# Port.net
KiCad netlist of a schematic drawn in Altium Designer
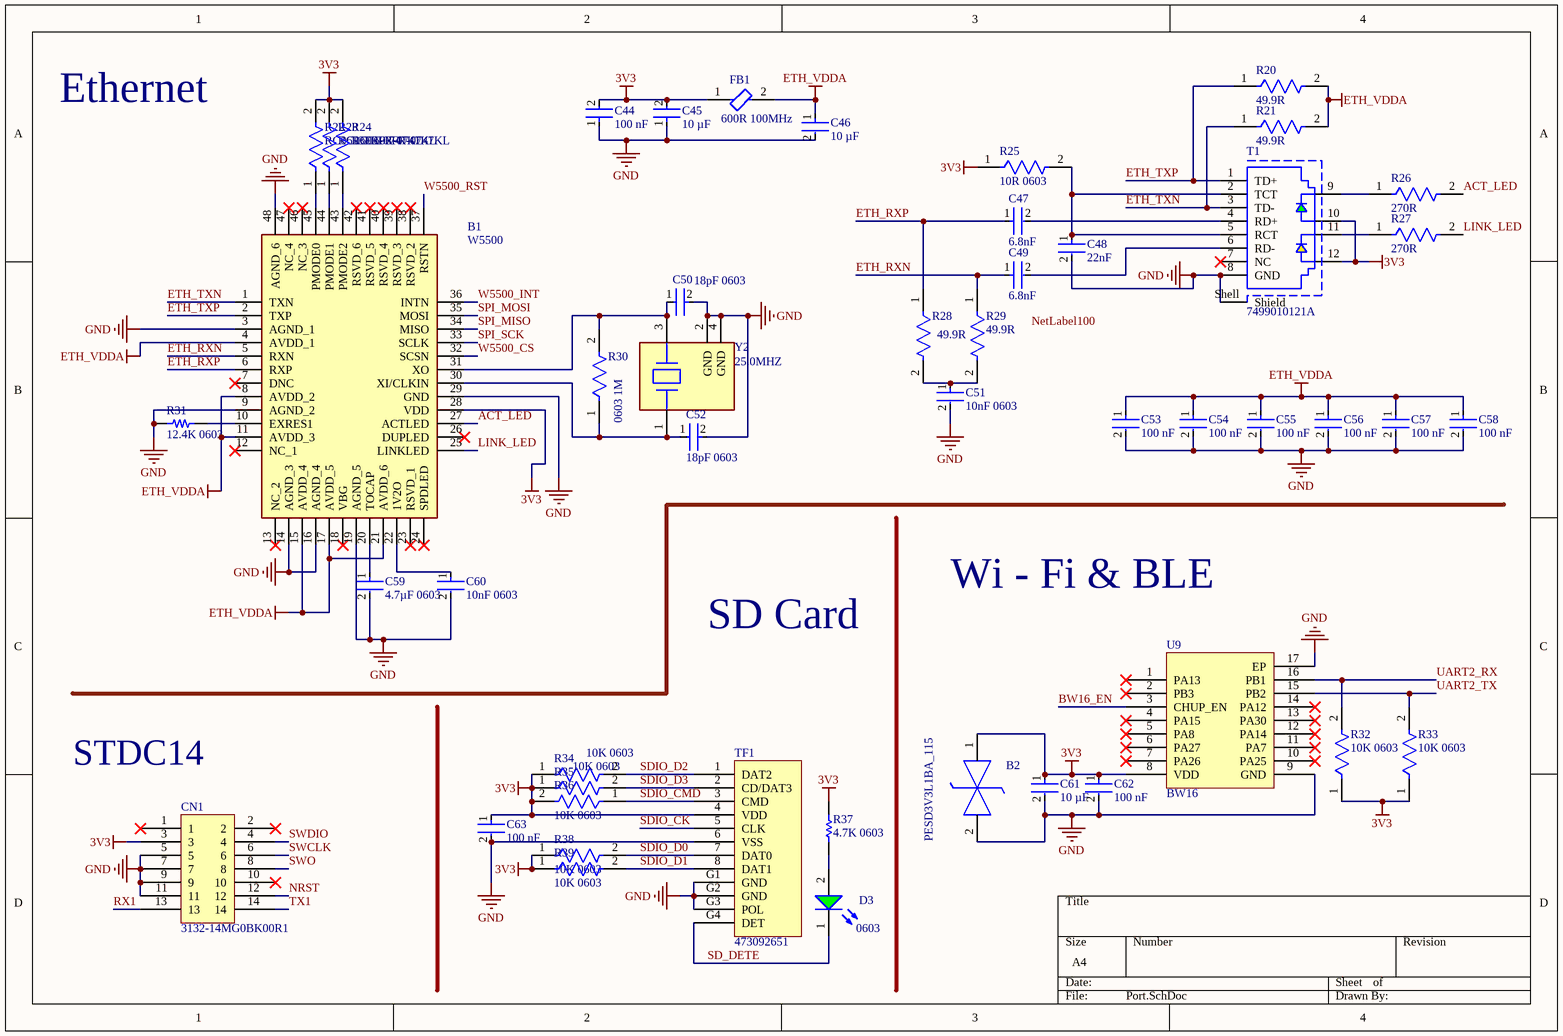
[diagram p0: Port.SchDoc]

(export (version "E")
  (design (tool "Eeschema 10.0.6"))
  (components
    (comp (ref "B1")
      (value "W5500")
      (footprint "W5500")
      (description "Ethernet ICs 3in1 Enet Controller TCP/IP +MAC+PHY")
      (fields (field (name "MOUSER PART NUMBER") "950-W5500"))
      (libsource (lib "Demo") (part "W5500"))
    )
    (comp (ref "B2")
      (value "PESD3V3L1BA_115")
      (footprint "SOD2512X110N")
      (description "PESD3V3L1BA - Low capacitance bidirectional ESD protection diode in SOD323")
      (fields
        (field (name "MANUFACTURER_PART_NUMBER") "PESD3V3L1BA,115")
        (field (name "MOUSER PART NUMBER") "771-PESD3V3L1BA-T/R")
      )
      (libsource (lib "Demo") (part "PESD3V3L1BA_115"))
    )
    (comp (ref "C44")
      (value "100 nF")
      (footprint "FP-CL10-IPC_A")
      (description "Cap Ceramic 100nF 100V X7R ±10% Pad SMD 0603 +125°C T/R")
      (fields (field (name "TOLERANCE") "10%"))
      (libsource (lib "Altium Content Vault") (part "b4654b650e69147ec39a6b967a45e02"))
    )
    (comp (ref "C45")
      (value "10 µF")
      (footprint "FP-CL10-IPC_C")
      (description "Cap Ceramic 10uF 25V X5R ±20% Pad SMD 0603 +85°C T/R")
      (fields (field (name "TOLERANCE") "20%"))
      (libsource (lib "Altium Content Vault") (part "b4654b650e69147ec39a6b967a45e02"))
    )
    (comp (ref "C46")
      (value "10 µF")
      (footprint "FP-CL10-IPC_C")
      (description "Cap Ceramic 10uF 25V X5R ±20% Pad SMD 0603 +85°C T/R")
      (fields (field (name "TOLERANCE") "20%"))
      (libsource (lib "Altium Content Vault") (part "b4654b650e69147ec39a6b967a45e02"))
    )
    (comp (ref "C47")
      (value "6.8nF")
      (footprint "FP-CC0603-DA-MFG")
      (description "CAP CER 6800PF 50V X7R 0603")
      (fields
        (field (name "OCTOPART") "https://octopart.com/cc0603krx7r9bb682-yageo-39467723")
        (field (name "TOLERANCE") "0.1")
      )
      (libsource (lib "Altium Content Vault") (part "11868f565c42a9108669ba33697ecf6"))
    )
    (comp (ref "C48")
      (value "22nF")
      (footprint "FP-CC0603-DA-MFG")
      (description "CAP CER 0.022UF 50V X7R 0603")
      (fields (field (name "TOLERANCE") "10%") (field (name "VOLTAGE") "50V"))
      (libsource (lib "Altium Content Vault") (part "11868f565c42a9108669ba33697ecf6"))
    )
    (comp (ref "C49")
      (value "6.8nF")
      (footprint "FP-CC0603-DA-MFG")
      (description "CAP CER 6800PF 50V X7R 0603")
      (fields
        (field (name "OCTOPART") "https://octopart.com/cc0603krx7r9bb682-yageo-39467723")
        (field (name "TOLERANCE") "0.1")
      )
      (libsource (lib "Altium Content Vault") (part "11868f565c42a9108669ba33697ecf6"))
    )
    (comp (ref "C50")
      (value "18pF 0603")
      (footprint "FP-C1608-080-0_1-IPC_C")
      (description "Multilayer Ceramic Capacitors 18pF ±5% 50V C0G SMD 0603")
      (fields (field (name "VOLTAGE") "50V") (field (name "TOLERANCE") "5%"))
      (libsource (lib "Altium Content Vault") (part "236180d848d6139a670b325ea6854c9"))
    )
    (comp (ref "C51")
      (value "10nF 0603")
      (footprint "FP-CC0603-DA-MFG")
      (description "CAP CER 10000PF 50V X7R 0603")
      (fields (field (name "TOLERANCE") "0.1") (field (name "MANUFACTURER PART NUMBER") "CC0603KRX7R9BB103"))
      (libsource (lib "Altium Content Vault") (part "11868f565c42a9108669ba33697ecf6"))
    )
    (comp (ref "C52")
      (value "18pF 0603")
      (footprint "FP-C1608-080-0_1-IPC_C")
      (description "Multilayer Ceramic Capacitors 18pF ±5% 50V C0G SMD 0603")
      (fields (field (name "VOLTAGE") "50V") (field (name "TOLERANCE") "5%"))
      (libsource (lib "Altium Content Vault") (part "236180d848d6139a670b325ea6854c9"))
    )
    (comp (ref "C53")
      (value "100 nF")
      (footprint "FP-CL10-IPC_A")
      (description "Cap Ceramic 100nF 100V X7R ±10% Pad SMD 0603 +125°C T/R")
      (fields (field (name "TOLERANCE") "10%"))
      (libsource (lib "Altium Content Vault") (part "b4654b650e69147ec39a6b967a45e02"))
    )
    (comp (ref "C54")
      (value "100 nF")
      (footprint "FP-CL10-IPC_A")
      (description "Cap Ceramic 100nF 100V X7R ±10% Pad SMD 0603 +125°C T/R")
      (fields (field (name "TOLERANCE") "10%"))
      (libsource (lib "Altium Content Vault") (part "b4654b650e69147ec39a6b967a45e02"))
    )
    (comp (ref "C55")
      (value "100 nF")
      (footprint "FP-CL10-IPC_A")
      (description "Cap Ceramic 100nF 100V X7R ±10% Pad SMD 0603 +125°C T/R")
      (fields (field (name "TOLERANCE") "10%"))
      (libsource (lib "Altium Content Vault") (part "b4654b650e69147ec39a6b967a45e02"))
    )
    (comp (ref "C56")
      (value "100 nF")
      (footprint "FP-CL10-IPC_A")
      (description "Cap Ceramic 100nF 100V X7R ±10% Pad SMD 0603 +125°C T/R")
      (fields (field (name "TOLERANCE") "10%"))
      (libsource (lib "Altium Content Vault") (part "b4654b650e69147ec39a6b967a45e02"))
    )
    (comp (ref "C57")
      (value "100 nF")
      (footprint "FP-CL10-IPC_A")
      (description "Cap Ceramic 100nF 100V X7R ±10% Pad SMD 0603 +125°C T/R")
      (fields (field (name "TOLERANCE") "10%"))
      (libsource (lib "Altium Content Vault") (part "b4654b650e69147ec39a6b967a45e02"))
    )
    (comp (ref "C58")
      (value "100 nF")
      (footprint "FP-CL10-IPC_A")
      (description "Cap Ceramic 100nF 100V X7R ±10% Pad SMD 0603 +125°C T/R")
      (fields (field (name "TOLERANCE") "10%"))
      (libsource (lib "Altium Content Vault") (part "b4654b650e69147ec39a6b967a45e02"))
    )
    (comp (ref "C59")
      (value "4.7µF 0603")
      (footprint "FP-C0603-CG-MFG")
      (description "CAP CER 4.7UF 6.3V X5R 0603")
      (fields (field (name "TOLERANCE") "10%") (field (name "MANUFACTURER") "Kemet"))
      (libsource (lib "Altium Content Vault") (part "11868f565c42a9108669ba33697ecf6"))
    )
    (comp (ref "C60")
      (value "10nF 0603")
      (footprint "FP-CC0603-DA-MFG")
      (description "CAP CER 10000PF 50V X7R 0603")
      (fields (field (name "TOLERANCE") "0.1") (field (name "MANUFACTURER PART NUMBER") "CC0603KRX7R9BB103"))
      (libsource (lib "Altium Content Vault") (part "11868f565c42a9108669ba33697ecf6"))
    )
    (comp (ref "C61")
      (value "10 µF")
      (footprint "FP-CL10-IPC_C")
      (description "Cap Ceramic 10uF 25V X5R ±20% Pad SMD 0603 +85°C T/R")
      (fields (field (name "TOLERANCE") "20%"))
      (libsource (lib "Altium Content Vault") (part "b4654b650e69147ec39a6b967a45e02"))
    )
    (comp (ref "C62")
      (value "100 nF")
      (footprint "FP-CL10-IPC_A")
      (description "Cap Ceramic 100nF 100V X7R ±10% Pad SMD 0603 +125°C T/R")
      (fields (field (name "TOLERANCE") "10%"))
      (libsource (lib "Altium Content Vault") (part "b4654b650e69147ec39a6b967a45e02"))
    )
    (comp (ref "C63")
      (value "100 nF")
      (footprint "FP-CL10-IPC_A")
      (description "Cap Ceramic 100nF 100V X7R ±10% Pad SMD 0603 +125°C T/R")
      (fields (field (name "TOLERANCE") "10%"))
      (libsource (lib "Altium Content Vault") (part "b4654b650e69147ec39a6b967a45e02"))
    )
    (comp (ref "CN1")
      (value "3132-14MG0BK00R1")
      (footprint "STDC14 Header")
      (libsource (lib "Demo") (part "STDC-14"))
    )
    (comp (ref "D3")
      (value "0603")
      (footprint "WL-SMCW_0603_150060xx75000")
      (libsource (lib "Altium Content Vault") (part "LED_Green_2A-1K"))
    )
    (comp (ref "FB1")
      (value "600R 100MHz")
      (footprint "FP-BLM18-0_15-t0_8-MFG")
      (description "Chip Ferrite Bead, 0603, 600Ω @ 100MHz, 0.38Ω, 25%, 500mA")
      (fields (field (name "TOLERANCE") "25%"))
      (libsource (lib "Altium Content Vault") (part "5f30dd21d616792df468990f7003faa"))
    )
    (comp (ref "R20")
      (value "49.9R")
      (footprint "FP-RT0603-MFG")
      (description "RES SMD 49.9OHM 0.05% 1/10W 0603")
      (fields (field (name "MANUFACTURER") "Yageo") (field (name "TOLERANCE") "0.0005"))
      (libsource (lib "Altium Content Vault") (part "1029c3af85768c4190bb7ad29bc67b5"))
    )
    (comp (ref "R21")
      (value "49.9R")
      (footprint "FP-RT0603-MFG")
      (description "RES SMD 49.9OHM 0.05% 1/10W 0603")
      (fields (field (name "MANUFACTURER") "Yageo") (field (name "TOLERANCE") "0.0005"))
      (libsource (lib "Altium Content Vault") (part "1029c3af85768c4190bb7ad29bc67b5"))
    )
    (comp (ref "R22")
      (value "RC0603FR-0747KL")
      (footprint "FP-RC0603FR-0747KL-MFG")
      (description "RES SMD 47K OHM 1% 1/10W 0603")
      (fields (field (name "TOLERANCE") "1%"))
      (libsource (lib "Altium Content Vault") (part "1029c3af85768c4190bb7ad29bc67b5"))
    )
    (comp (ref "R23")
      (value "RC0603FR-0747KL")
      (footprint "FP-RC0603FR-0747KL-MFG")
      (description "RES SMD 47K OHM 1% 1/10W 0603")
      (fields (field (name "TOLERANCE") "1%"))
      (libsource (lib "Altium Content Vault") (part "1029c3af85768c4190bb7ad29bc67b5"))
    )
    (comp (ref "R24")
      (value "RC0603FR-0747KL")
      (footprint "FP-RC0603FR-0747KL-MFG")
      (description "RES SMD 47K OHM 1% 1/10W 0603")
      (fields (field (name "TOLERANCE") "1%"))
      (libsource (lib "Altium Content Vault") (part "1029c3af85768c4190bb7ad29bc67b5"))
    )
    (comp (ref "R25")
      (value "10R 0603")
      (footprint "FP-RT0603-MFG")
      (description "RES SMD 10 OHM 0.5% 1/10W 0603")
      (fields (field (name "TOLERANCE") "0.005") (field (name "MANUFACTURER") "Yageo"))
      (libsource (lib "Altium Content Vault") (part "1029c3af85768c4190bb7ad29bc67b5"))
    )
    (comp (ref "R26")
      (value "270R")
      (footprint "FP-RT0603-MFG")
      (description "RES SMD 270 OHM 1% 1/10W 0603")
      (fields
        (field (name "OCTOPART") "https://octopart.com/rt0603fre07270rl-yageo-40014674")
        (field (name "TOLERANCE") "0.01")
      )
      (libsource (lib "Altium Content Vault") (part "1029c3af85768c4190bb7ad29bc67b5"))
    )
    (comp (ref "R27")
      (value "270R")
      (footprint "FP-RT0603-MFG")
      (description "RES SMD 270 OHM 1% 1/10W 0603")
      (fields
        (field (name "OCTOPART") "https://octopart.com/rt0603fre07270rl-yageo-40014674")
        (field (name "TOLERANCE") "0.01")
      )
      (libsource (lib "Altium Content Vault") (part "1029c3af85768c4190bb7ad29bc67b5"))
    )
    (comp (ref "R28")
      (value "49.9R")
      (footprint "FP-RT0603-MFG")
      (description "RES SMD 49.9OHM 0.05% 1/10W 0603")
      (fields (field (name "MANUFACTURER") "Yageo") (field (name "TOLERANCE") "0.0005"))
      (libsource (lib "Altium Content Vault") (part "1029c3af85768c4190bb7ad29bc67b5"))
    )
    (comp (ref "R29")
      (value "49.9R")
      (footprint "FP-RT0603-MFG")
      (description "RES SMD 49.9OHM 0.05% 1/10W 0603")
      (fields (field (name "MANUFACTURER") "Yageo") (field (name "TOLERANCE") "0.0005"))
      (libsource (lib "Altium Content Vault") (part "1029c3af85768c4190bb7ad29bc67b5"))
    )
    (comp (ref "R30")
      (value "0603 1M")
      (footprint "FP-RC0603-0_55-IPC_C")
      (description "RES SMD 1M OHM 5% 1/10W 0603")
      (fields (field (name "TOLERANCE") "5%"))
      (libsource (lib "Altium Content Vault") (part "1029c3af85768c4190bb7ad29bc67b5"))
    )
    (comp (ref "R31")
      (value "12.4K 0603")
      (footprint "4.7R")
      (description "SMT Resistor")
      (libsource (lib "Demo") (part "4.7R 0603"))
    )
    (comp (ref "R32")
      (value "10K 0603")
      (footprint "FP-RC0603-0_55-IPC_C")
      (description "RES 10K OHM 1% 1/10W 0603")
      (fields (field (name "TOLERANCE") "1%"))
      (libsource (lib "Altium Content Vault") (part "1029c3af85768c4190bb7ad29bc67b5"))
    )
    (comp (ref "R33")
      (value "10K 0603")
      (footprint "FP-RC0603-0_55-IPC_C")
      (description "RES 10K OHM 1% 1/10W 0603")
      (fields (field (name "TOLERANCE") "1%"))
      (libsource (lib "Altium Content Vault") (part "1029c3af85768c4190bb7ad29bc67b5"))
    )
    (comp (ref "R34")
      (value "10K 0603")
      (footprint "FP-RC0603-0_55-IPC_C")
      (description "RES 10K OHM 1% 1/10W 0603")
      (fields (field (name "TOLERANCE") "1%"))
      (libsource (lib "Altium Content Vault") (part "1029c3af85768c4190bb7ad29bc67b5"))
    )
    (comp (ref "R35")
      (value "10K 0603")
      (footprint "FP-RC0603-0_55-IPC_C")
      (description "RES 10K OHM 1% 1/10W 0603")
      (fields (field (name "TOLERANCE") "1%"))
      (libsource (lib "Altium Content Vault") (part "1029c3af85768c4190bb7ad29bc67b5"))
    )
    (comp (ref "R36")
      (value "10K 0603")
      (footprint "FP-RC0603-0_55-IPC_C")
      (description "RES 10K OHM 1% 1/10W 0603")
      (fields (field (name "TOLERANCE") "1%"))
      (libsource (lib "Altium Content Vault") (part "1029c3af85768c4190bb7ad29bc67b5"))
    )
    (comp (ref "R37")
      (value "4.7K 0603")
      (footprint "RESC1608X55X25LL10T15")
      (description "Chip Resistor, 4.7 KOhm, +/- 1%, 0.1 W, -55 to 155 degC, 0603 (1608 Metric), RoHS, Tape and Reel")
      (fields (field (name "MANUFACTURER") "Yageo") (field (name "TOLERANCE") "1%"))
      (libsource (lib "Altium Content Vault") (part "RES-2"))
    )
    (comp (ref "R38")
      (value "10K 0603")
      (footprint "FP-RC0603-0_55-IPC_C")
      (description "RES 10K OHM 1% 1/10W 0603")
      (fields (field (name "TOLERANCE") "1%"))
      (libsource (lib "Altium Content Vault") (part "1029c3af85768c4190bb7ad29bc67b5"))
    )
    (comp (ref "R39")
      (value "10K 0603")
      (footprint "FP-RC0603-0_55-IPC_C")
      (description "RES 10K OHM 1% 1/10W 0603")
      (fields (field (name "TOLERANCE") "1%"))
      (libsource (lib "Altium Content Vault") (part "1029c3af85768c4190bb7ad29bc67b5"))
    )
    (comp (ref "T1")
      (value "7499010121A")
      (footprint "7499010121A")
      (description "7499010121A Telecom and Datacom Connector, 8 Contact(s), Right Angle, Solder Terminal")
      (libsource (lib "Altium Content Vault") (part "7499010121A"))
    )
    (comp (ref "TF1")
      (value "473092651")
      (footprint "TF-SMD_47309-2285")
      (libsource (lib "Demo") (part "TF-SMD"))
    )
    (comp (ref "U9") (value "BW16") (footprint "BW16") (libsource (lib "Demo") (part "BW16")))
    (comp (ref "Y2")
      (value "25.0MHZ")
      (footprint "FP-ABM8G-MFG")
      (description "Crystal 25MHz ±20ppm (Tol) ±30ppm (Stability) 18pF FUND 60Ω 4-Pin SMD T/R")
      (fields (field (name "TOLERANCE") "20ppm"))
      (libsource (lib "Altium Content Vault") (part "48e526d86b7f2615d98721063c72f49"))
    )
  )
  (nets
    (net (code "1") (name "/ACT_LED") (class "Default")
      (node (ref "B1") (pin "27") (pinfunction "ACTLED_27") (pintype "passive"))
      (node (ref "R26") (pin "2") (pinfunction "2_2") (pintype "passive"))
    )
    (net (code "2") (name "/BW16_EN") (class "Default")
      (node (ref "U9") (pin "3") (pinfunction "CHUP_EN_3") (pintype "passive"))
    )
    (net (code "3") (name "/ETH_RXN") (class "Default")
      (node (ref "B1") (pin "5") (pinfunction "RXN_5") (pintype "passive"))
      (node (ref "C49") (pin "1") (pinfunction "1_1") (pintype "passive"))
      (node (ref "R29") (pin "1") (pinfunction "1_1") (pintype "passive"))
    )
    (net (code "4") (name "/ETH_RXP") (class "Default")
      (node (ref "B1") (pin "6") (pinfunction "RXP_6") (pintype "passive"))
      (node (ref "C47") (pin "1") (pinfunction "1_1") (pintype "passive"))
      (node (ref "R28") (pin "1") (pinfunction "1_1") (pintype "passive"))
    )
    (net (code "5") (name "/ETH_TXN") (class "Default")
      (node (ref "B1") (pin "1") (pinfunction "TXN_1") (pintype "passive"))
      (node (ref "R21") (pin "1") (pinfunction "1_1") (pintype "passive"))
      (node (ref "T1") (pin "3") (pinfunction "TD-_3") (pintype "passive"))
    )
    (net (code "6") (name "/ETH_TXP") (class "Default")
      (node (ref "B1") (pin "2") (pinfunction "TXP_2") (pintype "passive"))
      (node (ref "R20") (pin "1") (pinfunction "1_1") (pintype "passive"))
      (node (ref "T1") (pin "1") (pinfunction "TD+_1") (pintype "passive"))
    )
    (net (code "7") (name "/LINK_LED") (class "Default")
      (node (ref "B1") (pin "25") (pinfunction "LINKLED_25") (pintype "passive"))
      (node (ref "R27") (pin "2") (pinfunction "2_2") (pintype "passive"))
    )
    (net (code "8") (name "/NRST") (class "Default")
      (node (ref "CN1") (pin "12") (pinfunction "12_12") (pintype "passive"))
    )
    (net (code "10") (name "/RX1") (class "Default")
      (node (ref "CN1") (pin "13") (pinfunction "13_13") (pintype "passive"))
    )
    (net (code "11") (name "/SDIO_CK") (class "Default")
      (node (ref "TF1") (pin "5") (pinfunction "CLK_5") (pintype "passive"))
    )
    (net (code "12") (name "/SDIO_CMD") (class "Default")
      (node (ref "R36") (pin "1") (pinfunction "1_1") (pintype "passive"))
      (node (ref "TF1") (pin "3") (pinfunction "CMD_3") (pintype "passive"))
    )
    (net (code "13") (name "/SDIO_D0") (class "Default")
      (node (ref "R38") (pin "2") (pinfunction "2_2") (pintype "passive"))
      (node (ref "TF1") (pin "7") (pinfunction "DAT0_7") (pintype "passive"))
    )
    (net (code "14") (name "/SDIO_D1") (class "Default")
      (node (ref "R39") (pin "2") (pinfunction "2_2") (pintype "passive"))
      (node (ref "TF1") (pin "8") (pinfunction "DAT1_8") (pintype "passive"))
    )
    (net (code "15") (name "/SDIO_D2") (class "Default")
      (node (ref "R34") (pin "2") (pinfunction "2_2") (pintype "passive"))
      (node (ref "TF1") (pin "1") (pinfunction "DAT2_1") (pintype "passive"))
    )
    (net (code "16") (name "/SDIO_D3") (class "Default")
      (node (ref "R35") (pin "2") (pinfunction "2_2") (pintype "passive"))
      (node (ref "TF1") (pin "2") (pinfunction "CD/DAT3_2") (pintype "passive"))
    )
    (net (code "17") (name "/SD_DETE") (class "Default")
      (node (ref "D3") (pin "1") (pinfunction "K_1") (pintype "passive"))
      (node (ref "TF1") (pin "G4") (pinfunction "DET_G4") (pintype "passive"))
    )
    (net (code "18") (name "/SPI_MISO") (class "Default")
      (node (ref "B1") (pin "34") (pinfunction "MISO_34") (pintype "passive"))
    )
    (net (code "19") (name "/SPI_MOSI") (class "Default")
      (node (ref "B1") (pin "35") (pinfunction "MOSI_35") (pintype "passive"))
    )
    (net (code "20") (name "/SPI_SCK") (class "Default")
      (node (ref "B1") (pin "33") (pinfunction "SCLK_33") (pintype "passive"))
    )
    (net (code "21") (name "/SWCLK") (class "Default")
      (node (ref "CN1") (pin "6") (pinfunction "6_6") (pintype "passive"))
    )
    (net (code "22") (name "/SWDIO") (class "Default")
      (node (ref "CN1") (pin "4") (pinfunction "4_4") (pintype "passive"))
    )
    (net (code "23") (name "/SWO") (class "Default")
      (node (ref "CN1") (pin "8") (pinfunction "8_8") (pintype "passive"))
    )
    (net (code "24") (name "/TX1") (class "Default")
      (node (ref "CN1") (pin "14") (pinfunction "14_14") (pintype "passive"))
    )
    (net (code "25") (name "/UART2_RX") (class "Default")
      (node (ref "R32") (pin "2") (pinfunction "2_2") (pintype "passive"))
      (node (ref "U9") (pin "16") (pinfunction "PB1_16") (pintype "passive"))
    )
    (net (code "26") (name "/UART2_TX") (class "Default")
      (node (ref "R33") (pin "2") (pinfunction "2_2") (pintype "passive"))
      (node (ref "U9") (pin "15") (pinfunction "PB2_15") (pintype "passive"))
    )
    (net (code "27") (name "/W5500_CS") (class "Default")
      (node (ref "B1") (pin "32") (pinfunction "SCSN_32") (pintype "passive"))
    )
    (net (code "28") (name "/W5500_INT") (class "Default")
      (node (ref "B1") (pin "36") (pinfunction "INTN_36") (pintype "passive"))
    )
    (net (code "29") (name "/W5500_RST") (class "Default")
      (node (ref "B1") (pin "37") (pinfunction "RSTN_37") (pintype "passive"))
    )
    (net (code "30") (name "3V3") (class "Default")
      (node (ref "B1") (pin "28") (pinfunction "VDD_28") (pintype "passive"))
      (node (ref "B2") (pin "1") (pinfunction "K1_1") (pintype "passive"))
      (node (ref "C44") (pin "2") (pinfunction "2_2") (pintype "passive"))
      (node (ref "C45") (pin "2") (pinfunction "2_2") (pintype "passive"))
      (node (ref "C61") (pin "1") (pinfunction "1_1") (pintype "passive"))
      (node (ref "C62") (pin "1") (pinfunction "1_1") (pintype "passive"))
      (node (ref "C63") (pin "1") (pinfunction "1_1") (pintype "passive"))
      (node (ref "CN1") (pin "3") (pinfunction "3_3") (pintype "passive"))
      (node (ref "FB1") (pin "1") (pinfunction "1_1") (pintype "passive"))
      (node (ref "R22") (pin "2") (pinfunction "2_2") (pintype "passive"))
      (node (ref "R23") (pin "2") (pinfunction "2_2") (pintype "passive"))
      (node (ref "R24") (pin "2") (pinfunction "2_2") (pintype "passive"))
      (node (ref "R25") (pin "1") (pinfunction "1_1") (pintype "passive"))
      (node (ref "R32") (pin "1") (pinfunction "1_1") (pintype "passive"))
      (node (ref "R33") (pin "1") (pinfunction "1_1") (pintype "passive"))
      (node (ref "R34") (pin "1") (pinfunction "1_1") (pintype "passive"))
      (node (ref "R35") (pin "1") (pinfunction "1_1") (pintype "passive"))
      (node (ref "R36") (pin "2") (pinfunction "2_2") (pintype "passive"))
      (node (ref "R37") (pin "1") (pinfunction "1_1") (pintype "passive"))
      (node (ref "R38") (pin "1") (pinfunction "1_1") (pintype "passive"))
      (node (ref "R39") (pin "1") (pinfunction "1_1") (pintype "passive"))
      (node (ref "T1") (pin "10") (pinfunction "10_10") (pintype "passive"))
      (node (ref "T1") (pin "12") (pinfunction "12_12") (pintype "passive"))
      (node (ref "TF1") (pin "4") (pinfunction "VDD_4") (pintype "passive"))
      (node (ref "U9") (pin "8") (pinfunction "VDD_8") (pintype "passive"))
    )
    (net (code "31") (name "ETH_VDDA") (class "Default")
      (node (ref "B1") (pin "11") (pinfunction "AVDD_3_11") (pintype "passive"))
      (node (ref "B1") (pin "15") (pinfunction "AVDD_4_15") (pintype "passive"))
      (node (ref "B1") (pin "17") (pinfunction "AVDD_5_17") (pintype "passive"))
      (node (ref "B1") (pin "21") (pinfunction "AVDD_6_21") (pintype "passive"))
      (node (ref "B1") (pin "4") (pinfunction "AVDD_1_4") (pintype "passive"))
      (node (ref "B1") (pin "8") (pinfunction "AVDD_2_8") (pintype "passive"))
      (node (ref "C46") (pin "1") (pinfunction "1_1") (pintype "passive"))
      (node (ref "C53") (pin "1") (pinfunction "1_1") (pintype "passive"))
      (node (ref "C54") (pin "1") (pinfunction "1_1") (pintype "passive"))
      (node (ref "C55") (pin "1") (pinfunction "1_1") (pintype "passive"))
      (node (ref "C56") (pin "1") (pinfunction "1_1") (pintype "passive"))
      (node (ref "C57") (pin "1") (pinfunction "1_1") (pintype "passive"))
      (node (ref "C58") (pin "1") (pinfunction "1_1") (pintype "passive"))
      (node (ref "FB1") (pin "2") (pinfunction "2_2") (pintype "passive"))
      (node (ref "R20") (pin "2") (pinfunction "2_2") (pintype "passive"))
      (node (ref "R21") (pin "2") (pinfunction "2_2") (pintype "passive"))
    )
    (net (code "32") (name "GND") (class "Default")
      (node (ref "B1") (pin "14") (pinfunction "AGND_3_14") (pintype "passive"))
      (node (ref "B1") (pin "16") (pinfunction "AGND_4_16") (pintype "passive"))
      (node (ref "B1") (pin "19") (pinfunction "AGND_5_19") (pintype "passive"))
      (node (ref "B1") (pin "29") (pinfunction "GND_29") (pintype "passive"))
      (node (ref "B1") (pin "3") (pinfunction "AGND_1_3") (pintype "passive"))
      (node (ref "B1") (pin "48") (pinfunction "AGND_6_48") (pintype "passive"))
      (node (ref "B1") (pin "9") (pinfunction "AGND_2_9") (pintype "passive"))
      (node (ref "B2") (pin "2") (pinfunction "K2_2") (pintype "passive"))
      (node (ref "C44") (pin "1") (pinfunction "1_1") (pintype "passive"))
      (node (ref "C45") (pin "1") (pinfunction "1_1") (pintype "passive"))
      (node (ref "C46") (pin "2") (pinfunction "2_2") (pintype "passive"))
      (node (ref "C48") (pin "2") (pinfunction "2_2") (pintype "passive"))
      (node (ref "C50") (pin "2") (pinfunction "2_2") (pintype "passive"))
      (node (ref "C51") (pin "2") (pinfunction "2_2") (pintype "passive"))
      (node (ref "C52") (pin "2") (pinfunction "2_2") (pintype "passive"))
      (node (ref "C53") (pin "2") (pinfunction "2_2") (pintype "passive"))
      (node (ref "C54") (pin "2") (pinfunction "2_2") (pintype "passive"))
      (node (ref "C55") (pin "2") (pinfunction "2_2") (pintype "passive"))
      (node (ref "C56") (pin "2") (pinfunction "2_2") (pintype "passive"))
      (node (ref "C57") (pin "2") (pinfunction "2_2") (pintype "passive"))
      (node (ref "C58") (pin "2") (pinfunction "2_2") (pintype "passive"))
      (node (ref "C59") (pin "2") (pinfunction "2_2") (pintype "passive"))
      (node (ref "C60") (pin "2") (pinfunction "2_2") (pintype "passive"))
      (node (ref "C61") (pin "2") (pinfunction "2_2") (pintype "passive"))
      (node (ref "C62") (pin "2") (pinfunction "2_2") (pintype "passive"))
      (node (ref "C63") (pin "2") (pinfunction "2_2") (pintype "passive"))
      (node (ref "CN1") (pin "11") (pinfunction "11_11") (pintype "passive"))
      (node (ref "CN1") (pin "5") (pinfunction "5_5") (pintype "passive"))
      (node (ref "CN1") (pin "7") (pinfunction "7_7") (pintype "passive"))
      (node (ref "CN1") (pin "9") (pinfunction "9_9") (pintype "passive"))
      (node (ref "R31") (pin "2") (pinfunction "2_2") (pintype "passive"))
      (node (ref "T1") (pin "8") (pinfunction "GND_8") (pintype "passive"))
      (node (ref "T1") (pin "Shell") (pinfunction "Shield_Shell") (pintype "passive"))
      (node (ref "TF1") (pin "6") (pinfunction "VSS_6") (pintype "passive"))
      (node (ref "TF1") (pin "G1") (pinfunction "GND_G1") (pintype "passive"))
      (node (ref "TF1") (pin "G2") (pinfunction "GND_G2") (pintype "passive"))
      (node (ref "TF1") (pin "G3") (pinfunction "POL_G3") (pintype "passive"))
      (node (ref "U9") (pin "17") (pinfunction "EP_17") (pintype "passive"))
      (node (ref "U9") (pin "9") (pinfunction "GND_9") (pintype "passive"))
      (node (ref "Y2") (pin "2") (pinfunction "GND_2") (pintype "power_in"))
      (node (ref "Y2") (pin "4") (pinfunction "GND_4") (pintype "power_in"))
    )
    (net (code "33") (name "Net-(B1-1V2O)") (class "Default")
      (node (ref "B1") (pin "22") (pinfunction "1V2O_22") (pintype "passive"))
      (node (ref "C60") (pin "1") (pinfunction "1_1") (pintype "passive"))
    )
    (net (code "34") (name "Net-(B1-EXRES1)") (class "Default")
      (node (ref "B1") (pin "10") (pinfunction "EXRES1_10") (pintype "passive"))
      (node (ref "R31") (pin "1") (pinfunction "1_1") (pintype "passive"))
    )
    (net (code "35") (name "Net-(B1-PMODE0)") (class "Default")
      (node (ref "B1") (pin "45") (pinfunction "PMODE0_45") (pintype "passive"))
      (node (ref "R22") (pin "1") (pinfunction "1_1") (pintype "passive"))
    )
    (net (code "36") (name "Net-(B1-PMODE1)") (class "Default")
      (node (ref "B1") (pin "44") (pinfunction "PMODE1_44") (pintype "passive"))
      (node (ref "R23") (pin "1") (pinfunction "1_1") (pintype "passive"))
    )
    (net (code "37") (name "Net-(B1-PMODE2)") (class "Default")
      (node (ref "B1") (pin "43") (pinfunction "PMODE2_43") (pintype "passive"))
      (node (ref "R24") (pin "1") (pinfunction "1_1") (pintype "passive"))
    )
    (net (code "38") (name "Net-(B1-TOCAP)") (class "Default")
      (node (ref "B1") (pin "20") (pinfunction "TOCAP_20") (pintype "passive"))
      (node (ref "C59") (pin "1") (pinfunction "1_1") (pintype "passive"))
    )
    (net (code "39") (name "Net-(B1-XI{slash}CLKIN)") (class "Default")
      (node (ref "B1") (pin "30") (pinfunction "XI/CLKIN_30") (pintype "passive"))
      (node (ref "C52") (pin "1") (pinfunction "1_1") (pintype "passive"))
      (node (ref "R30") (pin "1") (pinfunction "1_1") (pintype "passive"))
      (node (ref "Y2") (pin "1") (pinfunction "1_1") (pintype "passive"))
    )
    (net (code "40") (name "Net-(B1-XO)") (class "Default")
      (node (ref "B1") (pin "31") (pinfunction "XO_31") (pintype "passive"))
      (node (ref "C50") (pin "1") (pinfunction "1_1") (pintype "passive"))
      (node (ref "R30") (pin "2") (pinfunction "2_2") (pintype "passive"))
      (node (ref "Y2") (pin "3") (pinfunction "3_3") (pintype "passive"))
    )
    (net (code "41") (name "Net-(C51-Pad1)") (class "Default")
      (node (ref "C51") (pin "1") (pinfunction "1_1") (pintype "passive"))
      (node (ref "R28") (pin "2") (pinfunction "2_2") (pintype "passive"))
      (node (ref "R29") (pin "2") (pinfunction "2_2") (pintype "passive"))
    )
    (net (code "42") (name "Net-(D3-A)") (class "Default")
      (node (ref "D3") (pin "2") (pinfunction "A_2") (pintype "passive"))
      (node (ref "R37") (pin "2") (pinfunction "2_2") (pintype "passive"))
    )
    (net (code "43") (name "Net-(R26-Pad1)") (class "Default")
      (node (ref "R26") (pin "1") (pinfunction "1_1") (pintype "passive"))
      (node (ref "T1") (pin "9") (pinfunction "9_9") (pintype "passive"))
    )
    (net (code "44") (name "Net-(R27-Pad1)") (class "Default")
      (node (ref "R27") (pin "1") (pinfunction "1_1") (pintype "passive"))
      (node (ref "T1") (pin "11") (pinfunction "11_11") (pintype "passive"))
    )
    (net (code "45") (name "Net-(T1-RCT)") (class "Default")
      (node (ref "C48") (pin "1") (pinfunction "1_1") (pintype "passive"))
      (node (ref "R25") (pin "2") (pinfunction "2_2") (pintype "passive"))
      (node (ref "T1") (pin "2") (pinfunction "TCT_2") (pintype "passive"))
      (node (ref "T1") (pin "5") (pinfunction "RCT_5") (pintype "passive"))
    )
    (net (code "46") (name "Net-(T1-RD+)") (class "Default")
      (node (ref "C47") (pin "2") (pinfunction "2_2") (pintype "passive"))
      (node (ref "T1") (pin "4") (pinfunction "RD+_4") (pintype "passive"))
    )
    (net (code "47") (name "Net-(T1-RD-)") (class "Default")
      (node (ref "C49") (pin "2") (pinfunction "2_2") (pintype "passive"))
      (node (ref "T1") (pin "6") (pinfunction "RD-_6") (pintype "passive"))
    )
    (net (code "48") (name "unconnected-(B1-DNC-Pad7)") (class "Default")
      (node (ref "B1") (pin "7") (pinfunction "DNC_7") (pintype "passive+no_connect"))
    )
    (net (code "49") (name "unconnected-(B1-DUPLED-Pad26)") (class "Default")
      (node (ref "B1") (pin "26") (pinfunction "DUPLED_26") (pintype "passive+no_connect"))
    )
    (net (code "50") (name "unconnected-(B1-NC_1-Pad12)") (class "Default")
      (node (ref "B1") (pin "12") (pinfunction "NC_1_12") (pintype "passive+no_connect"))
    )
    (net (code "51") (name "unconnected-(B1-NC_2-Pad13)") (class "Default")
      (node (ref "B1") (pin "13") (pinfunction "NC_2_13") (pintype "passive+no_connect"))
    )
    (net (code "52") (name "unconnected-(B1-NC_3-Pad46)") (class "Default")
      (node (ref "B1") (pin "46") (pinfunction "NC_3_46") (pintype "passive+no_connect"))
    )
    (net (code "53") (name "unconnected-(B1-NC_4-Pad47)") (class "Default")
      (node (ref "B1") (pin "47") (pinfunction "NC_4_47") (pintype "passive+no_connect"))
    )
    (net (code "54") (name "unconnected-(B1-RSVD_1-Pad23)") (class "Default")
      (node (ref "B1") (pin "23") (pinfunction "RSVD_1_23") (pintype "passive+no_connect"))
    )
    (net (code "55") (name "unconnected-(B1-RSVD_2-Pad38)") (class "Default")
      (node (ref "B1") (pin "38") (pinfunction "RSVD_2_38") (pintype "passive+no_connect"))
    )
    (net (code "56") (name "unconnected-(B1-RSVD_3-Pad39)") (class "Default")
      (node (ref "B1") (pin "39") (pinfunction "RSVD_3_39") (pintype "passive+no_connect"))
    )
    (net (code "57") (name "unconnected-(B1-RSVD_4-Pad40)") (class "Default")
      (node (ref "B1") (pin "40") (pinfunction "RSVD_4_40") (pintype "passive+no_connect"))
    )
    (net (code "58") (name "unconnected-(B1-RSVD_5-Pad41)") (class "Default")
      (node (ref "B1") (pin "41") (pinfunction "RSVD_5_41") (pintype "passive+no_connect"))
    )
    (net (code "59") (name "unconnected-(B1-RSVD_6-Pad42)") (class "Default")
      (node (ref "B1") (pin "42") (pinfunction "RSVD_6_42") (pintype "passive+no_connect"))
    )
    (net (code "60") (name "unconnected-(B1-SPDLED-Pad24)") (class "Default")
      (node (ref "B1") (pin "24") (pinfunction "SPDLED_24") (pintype "passive+no_connect"))
    )
    (net (code "61") (name "unconnected-(B1-VBG-Pad18)") (class "Default")
      (node (ref "B1") (pin "18") (pinfunction "VBG_18") (pintype "passive+no_connect"))
    )
    (net (code "62") (name "unconnected-(CN1-Pad1)") (class "Default")
      (node (ref "CN1") (pin "1") (pinfunction "1_1") (pintype "passive+no_connect"))
    )
    (net (code "63") (name "unconnected-(CN1-Pad2)") (class "Default")
      (node (ref "CN1") (pin "2") (pinfunction "2_2") (pintype "passive+no_connect"))
    )
    (net (code "64") (name "unconnected-(CN1-Pad10)") (class "Default")
      (node (ref "CN1") (pin "10") (pinfunction "10_10") (pintype "passive+no_connect"))
    )
    (net (code "65") (name "unconnected-(T1-NC-Pad7)") (class "Default")
      (node (ref "T1") (pin "7") (pinfunction "NC_7") (pintype "passive+no_connect"))
    )
    (net (code "66") (name "unconnected-(U9-PA7-Pad11)") (class "Default")
      (node (ref "U9") (pin "11") (pinfunction "PA7_11") (pintype "passive+no_connect"))
    )
    (net (code "67") (name "unconnected-(U9-PA8-Pad5)") (class "Default")
      (node (ref "U9") (pin "5") (pinfunction "PA8_5") (pintype "passive+no_connect"))
    )
    (net (code "68") (name "unconnected-(U9-PA12-Pad14)") (class "Default")
      (node (ref "U9") (pin "14") (pinfunction "PA12_14") (pintype "passive+no_connect"))
    )
    (net (code "69") (name "unconnected-(U9-PA13-Pad1)") (class "Default")
      (node (ref "U9") (pin "1") (pinfunction "PA13_1") (pintype "passive+no_connect"))
    )
    (net (code "70") (name "unconnected-(U9-PA14-Pad12)") (class "Default")
      (node (ref "U9") (pin "12") (pinfunction "PA14_12") (pintype "passive+no_connect"))
    )
    (net (code "71") (name "unconnected-(U9-PA15-Pad4)") (class "Default")
      (node (ref "U9") (pin "4") (pinfunction "PA15_4") (pintype "passive+no_connect"))
    )
    (net (code "72") (name "unconnected-(U9-PA25-Pad10)") (class "Default")
      (node (ref "U9") (pin "10") (pinfunction "PA25_10") (pintype "passive+no_connect"))
    )
    (net (code "73") (name "unconnected-(U9-PA26-Pad7)") (class "Default")
      (node (ref "U9") (pin "7") (pinfunction "PA26_7") (pintype "passive+no_connect"))
    )
    (net (code "74") (name "unconnected-(U9-PA27-Pad6)") (class "Default")
      (node (ref "U9") (pin "6") (pinfunction "PA27_6") (pintype "passive+no_connect"))
    )
    (net (code "75") (name "unconnected-(U9-PA30-Pad13)") (class "Default")
      (node (ref "U9") (pin "13") (pinfunction "PA30_13") (pintype "passive+no_connect"))
    )
    (net (code "76") (name "unconnected-(U9-PB3-Pad2)") (class "Default")
      (node (ref "U9") (pin "2") (pinfunction "PB3_2") (pintype "passive+no_connect"))
    )
  )
)
